# 04-External_Connectors.net
KiCad netlist of a schematic drawn in Altium Designer
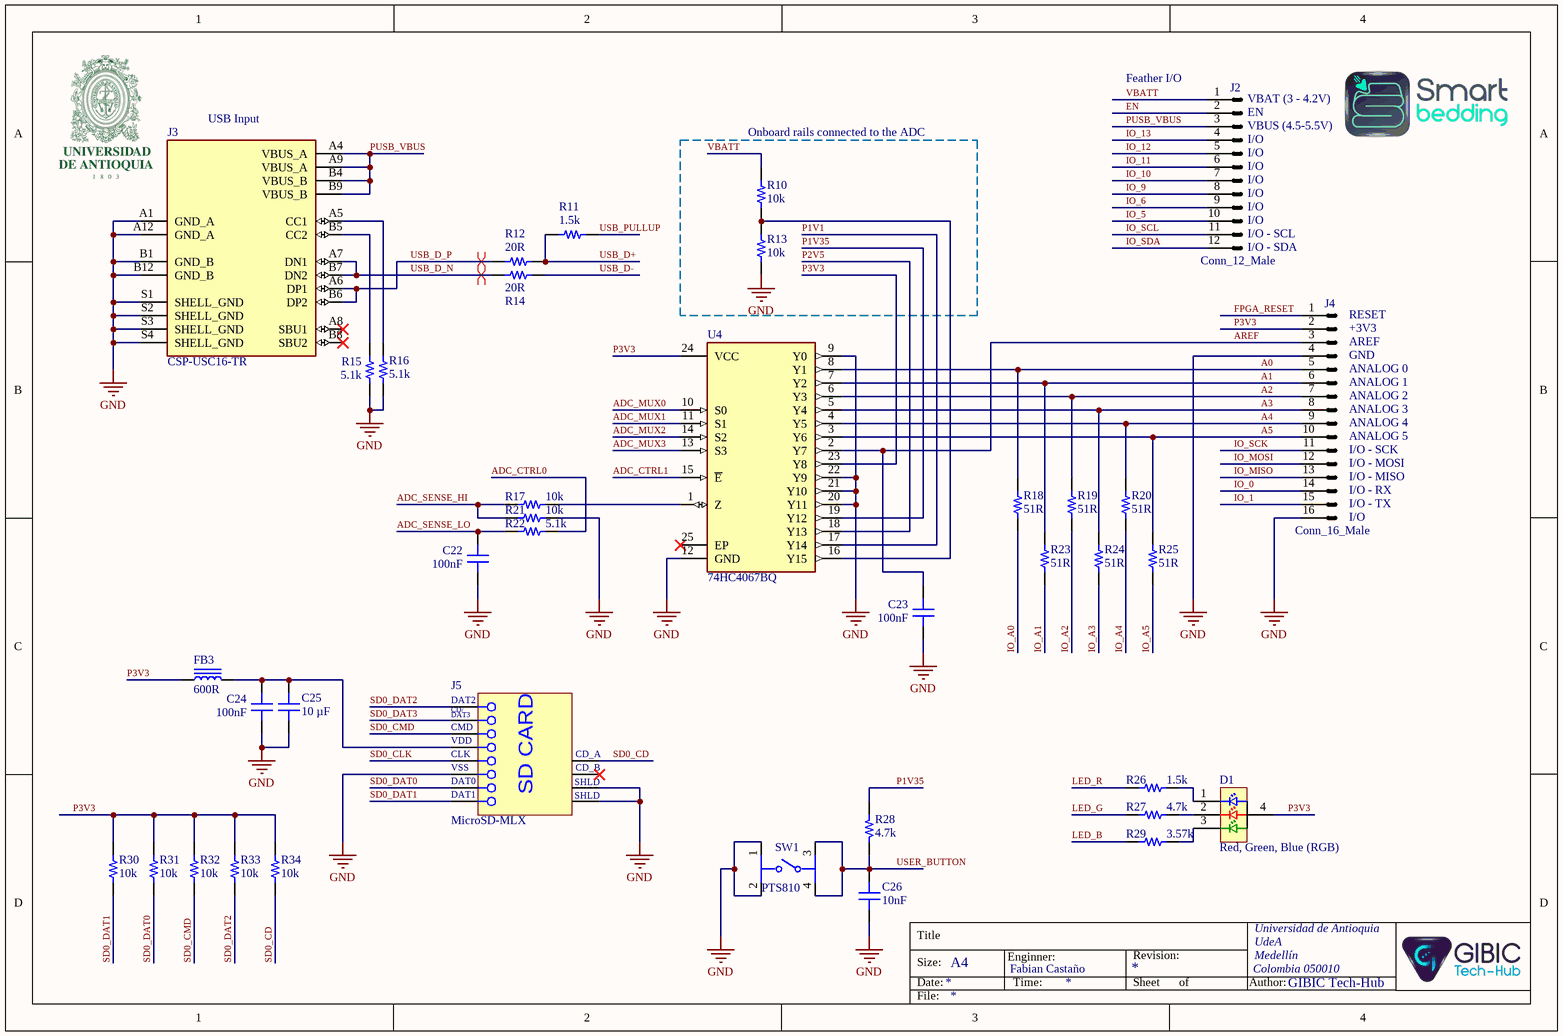
[diagram p0: 04-External_Connectors.SchDoc]

(export (version "E")
  (design (tool "Eeschema 10.0.6"))
  (components
    (comp (ref "C22")
      (value "100nF")
      (footprint "CAP 0201_0603")
      (description "CAP CER 0.1UF 6.3V X6S 0201")
      (fields
        (field (name "PART NUMBER") "GRT033C80J104KE01J")
        (field (name "MANUFACTURER") "Murata Electronics")
        (field (name "LASTUPDATED") "3/01/2023 8:00:58 p. m.")
      )
      (libsource (lib "Celestial Altium Library - altium_library") (part "Capacitor"))
    )
    (comp (ref "C23")
      (value "100nF")
      (footprint "CAP 0201_0603")
      (description "CAP CER 0.1UF 6.3V X6S 0201")
      (fields
        (field (name "PART NUMBER") "GRT033C80J104KE01J")
        (field (name "MANUFACTURER") "Murata Electronics")
        (field (name "LASTUPDATED") "3/01/2023 8:00:58 p. m.")
      )
      (libsource (lib "Celestial Altium Library - altium_library") (part "Capacitor"))
    )
    (comp (ref "C24")
      (value "100nF")
      (footprint "CAP 0201_0603")
      (description "CAP CER 0.1UF 6.3V X6S 0201")
      (fields
        (field (name "PART NUMBER") "GRT033C80J104KE01J")
        (field (name "MANUFACTURER") "Murata Electronics")
        (field (name "LASTUPDATED") "3/01/2023 8:00:58 p. m.")
      )
      (libsource (lib "Celestial Altium Library - altium_library") (part "Capacitor"))
    )
    (comp (ref "C25")
      (value "10 µF")
      (footprint "CAP 0402_1005")
      (description "CAP CER 10UF 10V X5R 0402")
      (fields
        (field (name "PART NUMBER") "CL05A106MP8NUB8")
        (field (name "MANUFACTURER") "Samsung Electro-Mechanics")
        (field (name "LASTUPDATED") "3/01/2023 8:04:20 p. m.")
      )
      (libsource (lib "Celestial Altium Library - altium_library") (part "Capacitor"))
    )
    (comp (ref "C26")
      (value "10nF")
      (footprint "CAP 0201_0603")
      (description "CAP CER 10000PF 10V X7R 0201")
      (fields
        (field (name "PART NUMBER") "0201ZC103JAT2A")
        (field (name "MANUFACTURER") "AVX Corporation")
        (field (name "LASTUPDATED") "2/09/2020 12:59:12 a. m.")
      )
      (libsource (lib "Celestial Altium Library - altium_library") (part "Capacitor"))
    )
    (comp (ref "D1")
      (value "Red, Green, Blue (RGB)")
      (footprint "Citizen CL-505S-X-SD-T")
      (description "LED TRI TOP FIRING 1.0 X 1.0")
      (fields
        (field (name "PART NUMBER") "CL-505S-X-SD-T")
        (field (name "MANUFACTURER") "Citizen")
        (field (name "LASTUPDATED") "19/03/2020 10:25:23 p. m.")
      )
      (libsource (lib "Celestial Altium Library - altium_library") (part "RGB LED Citizen CL-505"))
    )
    (comp (ref "FB3")
      (value "600R")
      (footprint "IND 0402_1005 RF WW")
      (description "FIXED IND 4.8NH 1.2A 71MOHM SMD")
      (fields
        (field (name "PART NUMBER") "LQW15AN4N8D8ZD")
        (field (name "MANUFACTURER") "Murata Electronics")
        (field (name "LASTUPDATED") "2/01/2023 8:59:34 p. m.")
      )
      (libsource (lib "Celestial Altium Library - altium_library") (part "Inductor"))
    )
    (comp (ref "J2")
      (value "Conn_12_Male")
      (footprint "Conn_12_Male")
      (description "Conn_01x12_Male")
      (libsource (lib "Conn_Male_Header") (part "Conn_12_Male"))
    )
    (comp (ref "J3")
      (value "CSP-USC16-TR")
      (footprint "VALCON_CSP-USC16-TR")
      (description "CSP-USC16-TR Valcon USB Type C Surface Mount PCB Socket")
      (fields (field (name "MF") "Valcon"))
      (libsource (lib "CSP-USC16-TR") (part "CSP-USC16-TR"))
    )
    (comp (ref "J4")
      (value "Conn_16_Male")
      (footprint "CONN_16_MALE")
      (description "Conn_01x16_Male")
      (libsource (lib "Conn_Male_Header") (part "Conn_16_Male"))
    )
    (comp (ref "J5")
      (value "MicroSD-MLX")
      (footprint "MOLEX-MicroSd")
      (description "Micro SD Card, RA, -25 to 85 degC, 8-Pin SMD, RoHS")
      (libsource (lib "MicroSd") (part "MicroSD-MLX"))
    )
    (comp (ref "R10")
      (value "10k")
      (footprint "RES 0201_0603")
      (description "RES SMD 10K OHM 0.1% 1/20W 0201")
      (fields
        (field (name "PART NUMBER") "ERA-1AEB103C")
        (field (name "MANUFACTURER") "Panasonic Electronic Components")
        (field (name "LASTUPDATED") "3/01/2023 8:15:23 p. m.")
      )
      (libsource (lib "Celestial Altium Library - altium_library") (part "Resistor"))
    )
    (comp (ref "R11")
      (value "1.5k")
      (footprint "RES 0201_0603")
      (description "RES SMD 10K OHM 0.1% 1/20W 0201")
      (fields
        (field (name "PART NUMBER") "ERA-1AEB103C")
        (field (name "MANUFACTURER") "Panasonic Electronic Components")
        (field (name "LASTUPDATED") "3/01/2023 8:15:23 p. m.")
      )
      (libsource (lib "Celestial Altium Library - altium_library") (part "Resistor"))
    )
    (comp (ref "R12")
      (value "20R")
      (footprint "RES 0201_0603")
      (description "RES SMD 10K OHM 0.1% 1/20W 0201")
      (fields
        (field (name "PART NUMBER") "ERA-1AEB103C")
        (field (name "MANUFACTURER") "Panasonic Electronic Components")
        (field (name "LASTUPDATED") "3/01/2023 8:15:23 p. m.")
      )
      (libsource (lib "Celestial Altium Library - altium_library") (part "Resistor"))
    )
    (comp (ref "R13")
      (value "10k")
      (footprint "RES 0201_0603")
      (description "RES SMD 10K OHM 0.1% 1/20W 0201")
      (fields
        (field (name "PART NUMBER") "ERA-1AEB103C")
        (field (name "MANUFACTURER") "Panasonic Electronic Components")
        (field (name "LASTUPDATED") "3/01/2023 8:15:23 p. m.")
      )
      (libsource (lib "Celestial Altium Library - altium_library") (part "Resistor"))
    )
    (comp (ref "R14")
      (value "20R")
      (footprint "RES 0201_0603")
      (description "RES SMD 10K OHM 0.1% 1/20W 0201")
      (fields
        (field (name "PART NUMBER") "ERA-1AEB103C")
        (field (name "MANUFACTURER") "Panasonic Electronic Components")
        (field (name "LASTUPDATED") "3/01/2023 8:15:23 p. m.")
      )
      (libsource (lib "Celestial Altium Library - altium_library") (part "Resistor"))
    )
    (comp (ref "R15")
      (value "5.1k")
      (footprint "RES 0201_0603")
      (description "RES SMD 10K OHM 0.1% 1/20W 0201")
      (fields
        (field (name "PART NUMBER") "ERA-1AEB103C")
        (field (name "MANUFACTURER") "Panasonic Electronic Components")
        (field (name "LASTUPDATED") "3/01/2023 8:15:23 p. m.")
      )
      (libsource (lib "Celestial Altium Library - altium_library") (part "Resistor"))
    )
    (comp (ref "R16")
      (value "5.1k")
      (footprint "RES 0201_0603")
      (description "RES SMD 10K OHM 0.1% 1/20W 0201")
      (fields
        (field (name "PART NUMBER") "ERA-1AEB103C")
        (field (name "MANUFACTURER") "Panasonic Electronic Components")
        (field (name "LASTUPDATED") "3/01/2023 8:15:23 p. m.")
      )
      (libsource (lib "Celestial Altium Library - altium_library") (part "Resistor"))
    )
    (comp (ref "R17")
      (value "10k")
      (footprint "RES 0201_0603")
      (description "RES SMD 10K OHM 0.1% 1/20W 0201")
      (fields
        (field (name "PART NUMBER") "ERA-1AEB103C")
        (field (name "MANUFACTURER") "Panasonic Electronic Components")
        (field (name "LASTUPDATED") "3/01/2023 8:15:23 p. m.")
      )
      (libsource (lib "Celestial Altium Library - altium_library") (part "Resistor"))
    )
    (comp (ref "R18")
      (value "51R")
      (footprint "RES 0201_0603")
      (description "RES SMD 10K OHM 0.1% 1/20W 0201")
      (fields
        (field (name "PART NUMBER") "ERA-1AEB103C")
        (field (name "MANUFACTURER") "Panasonic Electronic Components")
        (field (name "LASTUPDATED") "3/01/2023 8:15:23 p. m.")
      )
      (libsource (lib "Celestial Altium Library - altium_library") (part "Resistor"))
    )
    (comp (ref "R19")
      (value "51R")
      (footprint "RES 0201_0603")
      (description "RES SMD 10K OHM 0.1% 1/20W 0201")
      (fields
        (field (name "PART NUMBER") "ERA-1AEB103C")
        (field (name "MANUFACTURER") "Panasonic Electronic Components")
        (field (name "LASTUPDATED") "3/01/2023 8:15:23 p. m.")
      )
      (libsource (lib "Celestial Altium Library - altium_library") (part "Resistor"))
    )
    (comp (ref "R20")
      (value "51R")
      (footprint "RES 0201_0603")
      (description "RES SMD 10K OHM 0.1% 1/20W 0201")
      (fields
        (field (name "PART NUMBER") "ERA-1AEB103C")
        (field (name "MANUFACTURER") "Panasonic Electronic Components")
        (field (name "LASTUPDATED") "3/01/2023 8:15:23 p. m.")
      )
      (libsource (lib "Celestial Altium Library - altium_library") (part "Resistor"))
    )
    (comp (ref "R21")
      (value "10k")
      (footprint "RES 0201_0603")
      (description "RES SMD 10K OHM 0.1% 1/20W 0201")
      (fields
        (field (name "PART NUMBER") "ERA-1AEB103C")
        (field (name "MANUFACTURER") "Panasonic Electronic Components")
        (field (name "LASTUPDATED") "3/01/2023 8:15:23 p. m.")
      )
      (libsource (lib "Celestial Altium Library - altium_library") (part "Resistor"))
    )
    (comp (ref "R22")
      (value "5.1k")
      (footprint "RES 0201_0603")
      (description "RES SMD 10K OHM 0.1% 1/20W 0201")
      (fields
        (field (name "PART NUMBER") "ERA-1AEB103C")
        (field (name "MANUFACTURER") "Panasonic Electronic Components")
        (field (name "LASTUPDATED") "3/01/2023 8:15:23 p. m.")
      )
      (libsource (lib "Celestial Altium Library - altium_library") (part "Resistor"))
    )
    (comp (ref "R23")
      (value "51R")
      (footprint "RES 0201_0603")
      (description "RES SMD 10K OHM 0.1% 1/20W 0201")
      (fields
        (field (name "PART NUMBER") "ERA-1AEB103C")
        (field (name "MANUFACTURER") "Panasonic Electronic Components")
        (field (name "LASTUPDATED") "3/01/2023 8:15:23 p. m.")
      )
      (libsource (lib "Celestial Altium Library - altium_library") (part "Resistor"))
    )
    (comp (ref "R24")
      (value "51R")
      (footprint "RES 0201_0603")
      (description "RES SMD 10K OHM 0.1% 1/20W 0201")
      (fields
        (field (name "PART NUMBER") "ERA-1AEB103C")
        (field (name "MANUFACTURER") "Panasonic Electronic Components")
        (field (name "LASTUPDATED") "3/01/2023 8:15:23 p. m.")
      )
      (libsource (lib "Celestial Altium Library - altium_library") (part "Resistor"))
    )
    (comp (ref "R25")
      (value "51R")
      (footprint "RES 0201_0603")
      (description "RES SMD 10K OHM 0.1% 1/20W 0201")
      (fields
        (field (name "PART NUMBER") "ERA-1AEB103C")
        (field (name "MANUFACTURER") "Panasonic Electronic Components")
        (field (name "LASTUPDATED") "3/01/2023 8:15:23 p. m.")
      )
      (libsource (lib "Celestial Altium Library - altium_library") (part "Resistor"))
    )
    (comp (ref "R26")
      (value "1.5k")
      (footprint "RES 0201_0603")
      (description "RES SMD 10K OHM 0.1% 1/20W 0201")
      (fields
        (field (name "PART NUMBER") "ERA-1AEB103C")
        (field (name "MANUFACTURER") "Panasonic Electronic Components")
        (field (name "LASTUPDATED") "3/01/2023 8:15:23 p. m.")
      )
      (libsource (lib "Celestial Altium Library - altium_library") (part "Resistor"))
    )
    (comp (ref "R27")
      (value "4.7k")
      (footprint "RES 0201_0603")
      (description "RES SMD 10K OHM 0.1% 1/20W 0201")
      (fields
        (field (name "PART NUMBER") "ERA-1AEB103C")
        (field (name "MANUFACTURER") "Panasonic Electronic Components")
        (field (name "LASTUPDATED") "3/01/2023 8:15:23 p. m.")
      )
      (libsource (lib "Celestial Altium Library - altium_library") (part "Resistor"))
    )
    (comp (ref "R28")
      (value "4.7k")
      (footprint "RES 0201_0603")
      (description "RES SMD 10K OHM 0.1% 1/20W 0201")
      (fields
        (field (name "PART NUMBER") "ERA-1AEB103C")
        (field (name "MANUFACTURER") "Panasonic Electronic Components")
        (field (name "LASTUPDATED") "3/01/2023 8:15:23 p. m.")
      )
      (libsource (lib "Celestial Altium Library - altium_library") (part "Resistor"))
    )
    (comp (ref "R29")
      (value "3.57k")
      (footprint "RES 0201_0603")
      (description "RES SMD 10K OHM 0.1% 1/20W 0201")
      (fields
        (field (name "PART NUMBER") "ERA-1AEB103C")
        (field (name "MANUFACTURER") "Panasonic Electronic Components")
        (field (name "LASTUPDATED") "3/01/2023 8:15:23 p. m.")
      )
      (libsource (lib "Celestial Altium Library - altium_library") (part "Resistor"))
    )
    (comp (ref "R30")
      (value "10k")
      (footprint "RES 0201_0603")
      (description "RES SMD 10K OHM 0.1% 1/20W 0201")
      (fields
        (field (name "PART NUMBER") "ERA-1AEB103C")
        (field (name "MANUFACTURER") "Panasonic Electronic Components")
        (field (name "LASTUPDATED") "3/01/2023 8:15:23 p. m.")
      )
      (libsource (lib "Celestial Altium Library - altium_library") (part "Resistor"))
    )
    (comp (ref "R31")
      (value "10k")
      (footprint "RES 0201_0603")
      (description "RES SMD 10K OHM 0.1% 1/20W 0201")
      (fields
        (field (name "PART NUMBER") "ERA-1AEB103C")
        (field (name "MANUFACTURER") "Panasonic Electronic Components")
        (field (name "LASTUPDATED") "3/01/2023 8:15:23 p. m.")
      )
      (libsource (lib "Celestial Altium Library - altium_library") (part "Resistor"))
    )
    (comp (ref "R32")
      (value "10k")
      (footprint "RES 0201_0603")
      (description "RES SMD 10K OHM 0.1% 1/20W 0201")
      (fields
        (field (name "PART NUMBER") "ERA-1AEB103C")
        (field (name "MANUFACTURER") "Panasonic Electronic Components")
        (field (name "LASTUPDATED") "3/01/2023 8:15:23 p. m.")
      )
      (libsource (lib "Celestial Altium Library - altium_library") (part "Resistor"))
    )
    (comp (ref "R33")
      (value "10k")
      (footprint "RES 0201_0603")
      (description "RES SMD 10K OHM 0.1% 1/20W 0201")
      (fields
        (field (name "PART NUMBER") "ERA-1AEB103C")
        (field (name "MANUFACTURER") "Panasonic Electronic Components")
        (field (name "LASTUPDATED") "3/01/2023 8:15:23 p. m.")
      )
      (libsource (lib "Celestial Altium Library - altium_library") (part "Resistor"))
    )
    (comp (ref "R34")
      (value "10k")
      (footprint "RES 0201_0603")
      (description "RES SMD 10K OHM 0.1% 1/20W 0201")
      (fields
        (field (name "PART NUMBER") "ERA-1AEB103C")
        (field (name "MANUFACTURER") "Panasonic Electronic Components")
        (field (name "LASTUPDATED") "3/01/2023 8:15:23 p. m.")
      )
      (libsource (lib "Celestial Altium Library - altium_library") (part "Resistor"))
    )
    (comp (ref "SW1")
      (value "PTS810")
      (footprint "PCBComponent_1")
      (libsource (lib "PTS810") (part "PTS810"))
    )
    (comp (ref "U4")
      (value "74HC4067BQ")
      (footprint "QFN50P550X350X100-25N410X210")
      (description "1 Circuit IC Switch 16:1 120Ohm 24-DHVQFN _5.5x3.5_")
      (fields (field (name "MF") "Nexperia USA"))
      (libsource (lib "74HC4067BQ") (part "74HC4067BQ"))
    )
  )
  (nets
    (net (code "1") (name "/A0") (class "Default")
      (node (ref "J4") (pin "5") (pinfunction "5_5") (pintype "passive"))
      (node (ref "R18") (pin "2") (pinfunction "2_2") (pintype "passive"))
      (node (ref "U4") (pin "8") (pinfunction "Y1_8") (pintype "output"))
    )
    (net (code "2") (name "/A1") (class "Default")
      (node (ref "J4") (pin "6") (pinfunction "6_6") (pintype "passive"))
      (node (ref "R23") (pin "2") (pinfunction "2_2") (pintype "passive"))
      (node (ref "U4") (pin "7") (pinfunction "Y2_7") (pintype "output"))
    )
    (net (code "3") (name "/A2") (class "Default")
      (node (ref "J4") (pin "7") (pinfunction "7_7") (pintype "passive"))
      (node (ref "R19") (pin "2") (pinfunction "2_2") (pintype "passive"))
      (node (ref "U4") (pin "6") (pinfunction "Y3_6") (pintype "output"))
    )
    (net (code "4") (name "/A3") (class "Default")
      (node (ref "J4") (pin "8") (pinfunction "8_8") (pintype "passive"))
      (node (ref "R24") (pin "2") (pinfunction "2_2") (pintype "passive"))
      (node (ref "U4") (pin "5") (pinfunction "Y4_5") (pintype "output"))
    )
    (net (code "5") (name "/A4") (class "Default")
      (node (ref "J4") (pin "9") (pinfunction "9_9") (pintype "passive"))
      (node (ref "R20") (pin "2") (pinfunction "2_2") (pintype "passive"))
      (node (ref "U4") (pin "4") (pinfunction "Y5_4") (pintype "output"))
    )
    (net (code "6") (name "/A5") (class "Default")
      (node (ref "J4") (pin "10") (pinfunction "10_10") (pintype "passive"))
      (node (ref "R25") (pin "2") (pinfunction "2_2") (pintype "passive"))
      (node (ref "U4") (pin "3") (pinfunction "Y6_3") (pintype "output"))
    )
    (net (code "7") (name "/ADC_CTRL0") (class "Default")
      (node (ref "R22") (pin "1") (pinfunction "1_1") (pintype "passive"))
    )
    (net (code "8") (name "/ADC_CTRL1") (class "Default")
      (node (ref "U4") (pin "15") (pinfunction "~{E}_15") (pintype "input"))
    )
    (net (code "9") (name "/ADC_MUX0") (class "Default")
      (node (ref "U4") (pin "10") (pinfunction "S0_10") (pintype "input"))
    )
    (net (code "10") (name "/ADC_MUX1") (class "Default")
      (node (ref "U4") (pin "11") (pinfunction "S1_11") (pintype "input"))
    )
    (net (code "11") (name "/ADC_MUX2") (class "Default")
      (node (ref "U4") (pin "14") (pinfunction "S2_14") (pintype "input"))
    )
    (net (code "12") (name "/ADC_MUX3") (class "Default")
      (node (ref "U4") (pin "13") (pinfunction "S3_13") (pintype "input"))
    )
    (net (code "13") (name "/ADC_SENSE_HI") (class "Default")
      (node (ref "R17") (pin "2") (pinfunction "2_2") (pintype "passive"))
      (node (ref "R21") (pin "2") (pinfunction "2_2") (pintype "passive"))
    )
    (net (code "14") (name "/ADC_SENSE_LO") (class "Default")
      (node (ref "C22") (pin "2") (pinfunction "2_2") (pintype "passive"))
      (node (ref "R22") (pin "2") (pinfunction "2_2") (pintype "passive"))
    )
    (net (code "15") (name "/AREF") (class "Default")
      (node (ref "C23") (pin "2") (pinfunction "2_2") (pintype "passive"))
      (node (ref "J4") (pin "3") (pinfunction "3_3") (pintype "passive"))
      (node (ref "U4") (pin "2") (pinfunction "Y7_2") (pintype "output"))
    )
    (net (code "16") (name "/EN") (class "Default")
      (node (ref "J2") (pin "2") (pinfunction "2_2") (pintype "passive"))
    )
    (net (code "17") (name "/FPGA_RESET") (class "Default")
      (node (ref "J4") (pin "1") (pinfunction "1_1") (pintype "passive"))
    )
    (net (code "18") (name "/IO_0") (class "Default")
      (node (ref "J4") (pin "14") (pinfunction "14_14") (pintype "passive"))
    )
    (net (code "19") (name "/IO_1") (class "Default")
      (node (ref "J4") (pin "15") (pinfunction "15_15") (pintype "passive"))
    )
    (net (code "20") (name "/IO_5") (class "Default")
      (node (ref "J2") (pin "10") (pinfunction "10_10") (pintype "passive"))
    )
    (net (code "21") (name "/IO_6") (class "Default")
      (node (ref "J2") (pin "9") (pinfunction "9_9") (pintype "passive"))
    )
    (net (code "22") (name "/IO_9") (class "Default")
      (node (ref "J2") (pin "8") (pinfunction "8_8") (pintype "passive"))
    )
    (net (code "23") (name "/IO_10") (class "Default")
      (node (ref "J2") (pin "7") (pinfunction "7_7") (pintype "passive"))
    )
    (net (code "24") (name "/IO_11") (class "Default")
      (node (ref "J2") (pin "6") (pinfunction "6_6") (pintype "passive"))
    )
    (net (code "25") (name "/IO_12") (class "Default")
      (node (ref "J2") (pin "5") (pinfunction "5_5") (pintype "passive"))
    )
    (net (code "26") (name "/IO_13") (class "Default")
      (node (ref "J2") (pin "4") (pinfunction "4_4") (pintype "passive"))
    )
    (net (code "27") (name "/IO_A0") (class "Default")
      (node (ref "R18") (pin "1") (pinfunction "1_1") (pintype "passive"))
    )
    (net (code "28") (name "/IO_A1") (class "Default")
      (node (ref "R23") (pin "1") (pinfunction "1_1") (pintype "passive"))
    )
    (net (code "29") (name "/IO_A2") (class "Default")
      (node (ref "R19") (pin "1") (pinfunction "1_1") (pintype "passive"))
    )
    (net (code "30") (name "/IO_A3") (class "Default")
      (node (ref "R24") (pin "1") (pinfunction "1_1") (pintype "passive"))
    )
    (net (code "31") (name "/IO_A4") (class "Default")
      (node (ref "R20") (pin "1") (pinfunction "1_1") (pintype "passive"))
    )
    (net (code "32") (name "/IO_A5") (class "Default")
      (node (ref "R25") (pin "1") (pinfunction "1_1") (pintype "passive"))
    )
    (net (code "33") (name "/IO_MISO") (class "Default")
      (node (ref "J4") (pin "13") (pinfunction "13_13") (pintype "passive"))
    )
    (net (code "34") (name "/IO_MOSI") (class "Default")
      (node (ref "J4") (pin "12") (pinfunction "12_12") (pintype "passive"))
    )
    (net (code "35") (name "/IO_SCK") (class "Default")
      (node (ref "J4") (pin "11") (pinfunction "11_11") (pintype "passive"))
    )
    (net (code "36") (name "/IO_SCL") (class "Default")
      (node (ref "J2") (pin "11") (pinfunction "11_11") (pintype "passive"))
    )
    (net (code "37") (name "/IO_SDA") (class "Default")
      (node (ref "J2") (pin "12") (pinfunction "12_12") (pintype "passive"))
    )
    (net (code "38") (name "/LED_B") (class "Default")
      (node (ref "R29") (pin "2") (pinfunction "2_2") (pintype "passive"))
    )
    (net (code "39") (name "/LED_G") (class "Default")
      (node (ref "R27") (pin "2") (pinfunction "2_2") (pintype "passive"))
    )
    (net (code "40") (name "/LED_R") (class "Default")
      (node (ref "R26") (pin "2") (pinfunction "2_2") (pintype "passive"))
    )
    (net (code "41") (name "/P1V1") (class "Default")
      (node (ref "U4") (pin "17") (pinfunction "Y14_17") (pintype "output"))
    )
    (net (code "42") (name "/P1V35") (class "Default")
      (node (ref "R28") (pin "2") (pinfunction "2_2") (pintype "passive"))
      (node (ref "U4") (pin "19") (pinfunction "Y12_19") (pintype "output"))
    )
    (net (code "43") (name "/P2V5") (class "Default")
      (node (ref "U4") (pin "18") (pinfunction "Y13_18") (pintype "output"))
    )
    (net (code "44") (name "/P3V3") (class "Default")
      (node (ref "D1") (pin "4") (pinfunction "A3_4") (pintype "passive"))
      (node (ref "FB3") (pin "1") (pinfunction "1_1") (pintype "passive"))
      (node (ref "J4") (pin "2") (pinfunction "2_2") (pintype "passive"))
      (node (ref "R30") (pin "2") (pinfunction "2_2") (pintype "passive"))
      (node (ref "R31") (pin "2") (pinfunction "2_2") (pintype "passive"))
      (node (ref "R32") (pin "2") (pinfunction "2_2") (pintype "passive"))
      (node (ref "R33") (pin "2") (pinfunction "2_2") (pintype "passive"))
      (node (ref "R34") (pin "2") (pinfunction "2_2") (pintype "passive"))
      (node (ref "U4") (pin "23") (pinfunction "Y8_23") (pintype "output"))
      (node (ref "U4") (pin "24") (pinfunction "VCC_24") (pintype "power_in"))
    )
    (net (code "45") (name "/PUSB_VBUS") (class "Default")
      (node (ref "J2") (pin "3") (pinfunction "3_3") (pintype "passive"))
      (node (ref "J3") (pin "A4") (pinfunction "VBUS_A_A4") (pintype "power_in"))
      (node (ref "J3") (pin "A9") (pinfunction "VBUS_A_A9") (pintype "power_in"))
      (node (ref "J3") (pin "B4") (pinfunction "VBUS_B_B4") (pintype "power_in"))
      (node (ref "J3") (pin "B9") (pinfunction "VBUS_B_B9") (pintype "power_in"))
    )
    (net (code "46") (name "/SD0_CD") (class "Default")
      (node (ref "J5") (pin "9") (pinfunction "CD_A_9") (pintype "passive"))
      (node (ref "R34") (pin "1") (pinfunction "1_1") (pintype "passive"))
    )
    (net (code "47") (name "/SD0_CLK") (class "Default")
      (node (ref "J5") (pin "5") (pinfunction "CLK_5") (pintype "passive"))
    )
    (net (code "48") (name "/SD0_CMD") (class "Default")
      (node (ref "J5") (pin "3") (pinfunction "CMD_3") (pintype "passive"))
      (node (ref "R32") (pin "1") (pinfunction "1_1") (pintype "passive"))
    )
    (net (code "49") (name "/SD0_DAT0") (class "Default")
      (node (ref "J5") (pin "7") (pinfunction "DAT0_7") (pintype "passive"))
      (node (ref "R31") (pin "1") (pinfunction "1_1") (pintype "passive"))
    )
    (net (code "50") (name "/SD0_DAT1") (class "Default")
      (node (ref "J5") (pin "8") (pinfunction "DAT1_8") (pintype "passive"))
      (node (ref "R30") (pin "1") (pinfunction "1_1") (pintype "passive"))
    )
    (net (code "51") (name "/SD0_DAT2") (class "Default")
      (node (ref "J5") (pin "1") (pinfunction "DAT2_1") (pintype "passive"))
      (node (ref "R33") (pin "1") (pinfunction "1_1") (pintype "passive"))
    )
    (net (code "52") (name "/SD0_DAT3") (class "Default")
      (node (ref "J5") (pin "2") (pinfunction "CD/DAT3_2") (pintype "passive"))
    )
    (net (code "53") (name "/USB_D+") (class "Default")
      (node (ref "R11") (pin "2") (pinfunction "2_2") (pintype "passive"))
      (node (ref "R12") (pin "1") (pinfunction "1_1") (pintype "passive"))
    )
    (net (code "54") (name "/USB_D-") (class "Default")
      (node (ref "R14") (pin "1") (pinfunction "1_1") (pintype "passive"))
    )
    (net (code "55") (name "/USB_D_N") (class "Default")
      (node (ref "J3") (pin "A7") (pinfunction "DN1_A7") (pintype "bidirectional"))
      (node (ref "J3") (pin "B7") (pinfunction "DN2_B7") (pintype "bidirectional"))
      (node (ref "R14") (pin "2") (pinfunction "2_2") (pintype "passive"))
    )
    (net (code "56") (name "/USB_D_P") (class "Default")
      (node (ref "J3") (pin "A6") (pinfunction "DP1_A6") (pintype "bidirectional"))
      (node (ref "J3") (pin "B6") (pinfunction "DP2_B6") (pintype "bidirectional"))
      (node (ref "R12") (pin "2") (pinfunction "2_2") (pintype "passive"))
    )
    (net (code "57") (name "/USB_PULLUP") (class "Default")
      (node (ref "R11") (pin "1") (pinfunction "1_1") (pintype "passive"))
    )
    (net (code "58") (name "/USER_BUTTON") (class "Default")
      (node (ref "C26") (pin "2") (pinfunction "2_2") (pintype "passive"))
      (node (ref "R28") (pin "1") (pinfunction "1_1") (pintype "passive"))
      (node (ref "SW1") (pin "3") (pinfunction "3_3") (pintype "passive"))
      (node (ref "SW1") (pin "4") (pinfunction "4_4") (pintype "passive"))
    )
    (net (code "59") (name "/VBATT") (class "Default")
      (node (ref "J2") (pin "1") (pinfunction "1_1") (pintype "passive"))
      (node (ref "R10") (pin "2") (pinfunction "2_2") (pintype "passive"))
    )
    (net (code "60") (name "GND") (class "Default")
      (node (ref "C22") (pin "1") (pinfunction "1_1") (pintype "passive"))
      (node (ref "C23") (pin "1") (pinfunction "1_1") (pintype "passive"))
      (node (ref "C24") (pin "1") (pinfunction "1_1") (pintype "passive"))
      (node (ref "C25") (pin "1") (pinfunction "1_1") (pintype "passive"))
      (node (ref "C26") (pin "1") (pinfunction "1_1") (pintype "passive"))
      (node (ref "J3") (pin "A1") (pinfunction "GND_A_A1") (pintype "power_in"))
      (node (ref "J3") (pin "A12") (pinfunction "GND_A_A12") (pintype "power_in"))
      (node (ref "J3") (pin "B1") (pinfunction "GND_B_B1") (pintype "power_in"))
      (node (ref "J3") (pin "B12") (pinfunction "GND_B_B12") (pintype "power_in"))
      (node (ref "J3") (pin "S1") (pinfunction "SHELL_GND_S1") (pintype "power_in"))
      (node (ref "J3") (pin "S2") (pinfunction "SHELL_GND_S2") (pintype "power_in"))
      (node (ref "J3") (pin "S3") (pinfunction "SHELL_GND_S3") (pintype "power_in"))
      (node (ref "J3") (pin "S4") (pinfunction "SHELL_GND_S4") (pintype "power_in"))
      (node (ref "J4") (pin "16") (pinfunction "16_16") (pintype "passive"))
      (node (ref "J4") (pin "4") (pinfunction "4_4") (pintype "passive"))
      (node (ref "J5") (pin "11") (pinfunction "SHLD1_11") (pintype "passive"))
      (node (ref "J5") (pin "12") (pinfunction "SHLD2_12") (pintype "passive"))
      (node (ref "J5") (pin "6") (pinfunction "VSS_6") (pintype "passive"))
      (node (ref "R13") (pin "1") (pinfunction "1_1") (pintype "passive"))
      (node (ref "R15") (pin "1") (pinfunction "1_1") (pintype "passive"))
      (node (ref "R16") (pin "1") (pinfunction "1_1") (pintype "passive"))
      (node (ref "R21") (pin "1") (pinfunction "1_1") (pintype "passive"))
      (node (ref "SW1") (pin "1") (pinfunction "1_1") (pintype "passive"))
      (node (ref "SW1") (pin "2") (pinfunction "2_2") (pintype "passive"))
      (node (ref "U4") (pin "12") (pinfunction "GND_12") (pintype "power_in"))
      (node (ref "U4") (pin "20") (pinfunction "Y11_20") (pintype "output"))
      (node (ref "U4") (pin "21") (pinfunction "Y10_21") (pintype "output"))
      (node (ref "U4") (pin "22") (pinfunction "Y9_22") (pintype "output"))
      (node (ref "U4") (pin "9") (pinfunction "Y0_9") (pintype "output"))
    )
    (net (code "61") (name "Net-(D1-C1)") (class "Default")
      (node (ref "D1") (pin "1") (pinfunction "C1_1") (pintype "passive"))
      (node (ref "R26") (pin "1") (pinfunction "1_1") (pintype "passive"))
    )
    (net (code "62") (name "Net-(D1-C2)") (class "Default")
      (node (ref "D1") (pin "2") (pinfunction "C2_2") (pintype "passive"))
      (node (ref "R27") (pin "1") (pinfunction "1_1") (pintype "passive"))
    )
    (net (code "63") (name "Net-(D1-C3)") (class "Default")
      (node (ref "D1") (pin "3") (pinfunction "C3_3") (pintype "passive"))
      (node (ref "R29") (pin "1") (pinfunction "1_1") (pintype "passive"))
    )
    (net (code "64") (name "Net-(J3-CC1)") (class "Default")
      (node (ref "J3") (pin "A5") (pinfunction "CC1_A5") (pintype "bidirectional"))
      (node (ref "R16") (pin "2") (pinfunction "2_2") (pintype "passive"))
    )
    (net (code "65") (name "Net-(J3-CC2)") (class "Default")
      (node (ref "J3") (pin "B5") (pinfunction "CC2_B5") (pintype "bidirectional"))
      (node (ref "R15") (pin "2") (pinfunction "2_2") (pintype "passive"))
    )
    (net (code "66") (name "Net-(J5-VDD)") (class "Default")
      (node (ref "C24") (pin "2") (pinfunction "2_2") (pintype "passive"))
      (node (ref "C25") (pin "2") (pinfunction "2_2") (pintype "passive"))
      (node (ref "FB3") (pin "2") (pinfunction "2_2") (pintype "passive"))
      (node (ref "J5") (pin "4") (pinfunction "VDD_4") (pintype "passive"))
    )
    (net (code "67") (name "Net-(U4-Y15)") (class "Default")
      (node (ref "R10") (pin "1") (pinfunction "1_1") (pintype "passive"))
      (node (ref "R13") (pin "2") (pinfunction "2_2") (pintype "passive"))
      (node (ref "U4") (pin "16") (pinfunction "Y15_16") (pintype "output"))
    )
    (net (code "68") (name "Net-(U4-Z)") (class "Default")
      (node (ref "R17") (pin "1") (pinfunction "1_1") (pintype "passive"))
      (node (ref "U4") (pin "1") (pinfunction "Z_1") (pintype "bidirectional"))
    )
    (net (code "69") (name "unconnected-(J3-SBU1-PadA8)") (class "Default")
      (node (ref "J3") (pin "A8") (pinfunction "SBU1_A8") (pintype "bidirectional+no_connect"))
    )
    (net (code "70") (name "unconnected-(J3-SBU2-PadB8)") (class "Default")
      (node (ref "J3") (pin "B8") (pinfunction "SBU2_B8") (pintype "bidirectional+no_connect"))
    )
    (net (code "71") (name "unconnected-(J5-CD_B-Pad10)") (class "Default")
      (node (ref "J5") (pin "10") (pinfunction "CD_B_10") (pintype "passive+no_connect"))
    )
    (net (code "72") (name "unconnected-(U4-EP-Pad25)") (class "Default")
      (node (ref "U4") (pin "25") (pinfunction "EP_25") (pintype "power_in+no_connect"))
    )
  )
)
